# MCU.net
KiCad netlist of a schematic drawn in Altium Designer
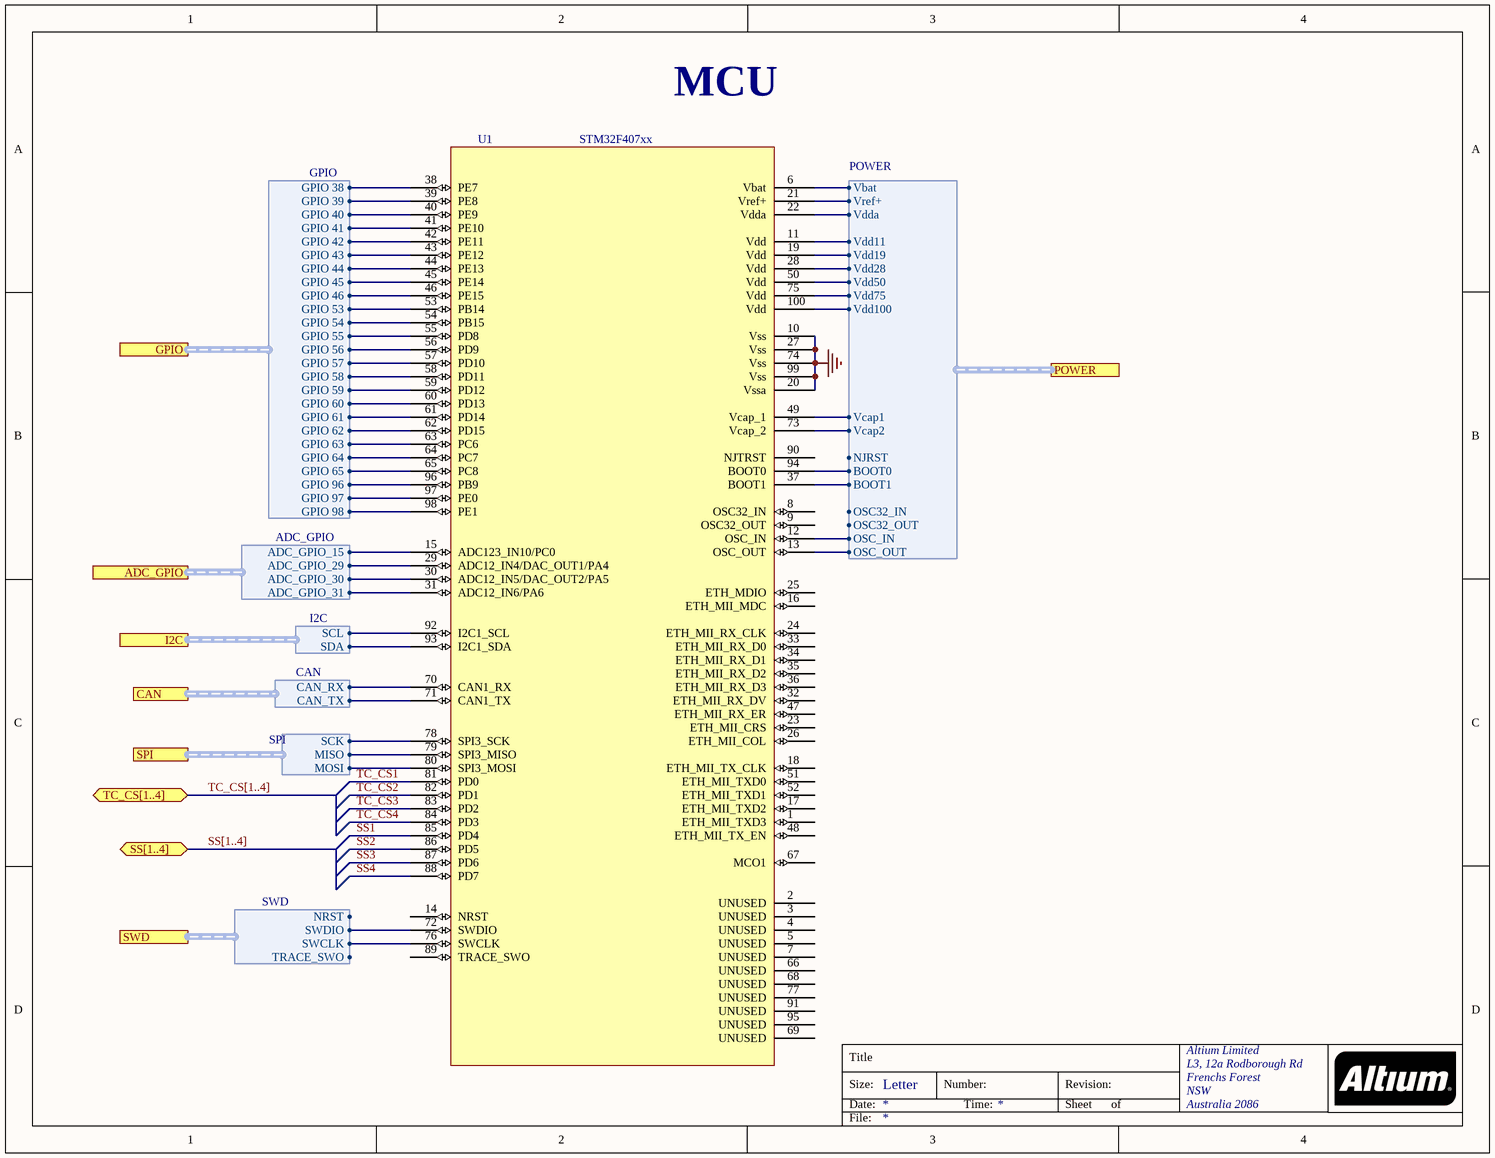
[diagram p0: MCU.SchDoc]

(export (version "E")
  (design (tool "Eeschema 10.0.6"))
  (components
    (comp (ref "U1")
      (value "STM32F407xx")
      (footprint "LQFP100")
      (libsource (lib "LaunchyRIOComponents") (part "STM32F407xx"))
    )
  )
  (nets
    (net (code "8") (name "/ADC_GPIO_15") (class "Default")
      (node (ref "U1") (pin "15") (pinfunction "ADC123_IN10/PC0_15") (pintype "bidirectional"))
    )
    (net (code "9") (name "/ADC_GPIO_29") (class "Default")
      (node (ref "U1") (pin "29") (pinfunction "ADC12_IN4/DAC_OUT1/PA4_29") (pintype "bidirectional"))
    )
    (net (code "10") (name "/ADC_GPIO_30") (class "Default")
      (node (ref "U1") (pin "30") (pinfunction "ADC12_IN5/DAC_OUT2/PA5_30") (pintype "bidirectional"))
    )
    (net (code "11") (name "/ADC_GPIO_31") (class "Default")
      (node (ref "U1") (pin "31") (pinfunction "ADC12_IN6/PA6_31") (pintype "bidirectional"))
    )
    (net (code "12") (name "/BOOT0") (class "Default")
      (node (ref "U1") (pin "94") (pinfunction "BOOT0_94") (pintype "passive"))
    )
    (net (code "13") (name "/BOOT1") (class "Default")
      (node (ref "U1") (pin "37") (pinfunction "BOOT1_37") (pintype "passive"))
    )
    (net (code "14") (name "/CAN_RX") (class "Default")
      (node (ref "U1") (pin "70") (pinfunction "CAN1_RX_70") (pintype "bidirectional"))
    )
    (net (code "15") (name "/CAN_TX") (class "Default")
      (node (ref "U1") (pin "71") (pinfunction "CAN1_TX_71") (pintype "bidirectional"))
    )
    (net (code "16") (name "/GPIO 38") (class "Default")
      (node (ref "U1") (pin "38") (pinfunction "PE7_38") (pintype "bidirectional"))
    )
    (net (code "17") (name "/GPIO 39") (class "Default")
      (node (ref "U1") (pin "39") (pinfunction "PE8_39") (pintype "bidirectional"))
    )
    (net (code "18") (name "/GPIO 40") (class "Default")
      (node (ref "U1") (pin "40") (pinfunction "PE9_40") (pintype "bidirectional"))
    )
    (net (code "19") (name "/GPIO 41") (class "Default")
      (node (ref "U1") (pin "41") (pinfunction "PE10_41") (pintype "bidirectional"))
    )
    (net (code "20") (name "/GPIO 42") (class "Default")
      (node (ref "U1") (pin "42") (pinfunction "PE11_42") (pintype "bidirectional"))
    )
    (net (code "21") (name "/GPIO 43") (class "Default")
      (node (ref "U1") (pin "43") (pinfunction "PE12_43") (pintype "bidirectional"))
    )
    (net (code "22") (name "/GPIO 44") (class "Default")
      (node (ref "U1") (pin "44") (pinfunction "PE13_44") (pintype "bidirectional"))
    )
    (net (code "23") (name "/GPIO 45") (class "Default")
      (node (ref "U1") (pin "45") (pinfunction "PE14_45") (pintype "bidirectional"))
    )
    (net (code "24") (name "/GPIO 46") (class "Default")
      (node (ref "U1") (pin "46") (pinfunction "PE15_46") (pintype "bidirectional"))
    )
    (net (code "25") (name "/GPIO 53") (class "Default")
      (node (ref "U1") (pin "53") (pinfunction "PB14_53") (pintype "bidirectional"))
    )
    (net (code "26") (name "/GPIO 54") (class "Default")
      (node (ref "U1") (pin "54") (pinfunction "PB15_54") (pintype "bidirectional"))
    )
    (net (code "27") (name "/GPIO 55") (class "Default")
      (node (ref "U1") (pin "55") (pinfunction "PD8_55") (pintype "bidirectional"))
    )
    (net (code "28") (name "/GPIO 56") (class "Default")
      (node (ref "U1") (pin "56") (pinfunction "PD9_56") (pintype "bidirectional"))
    )
    (net (code "29") (name "/GPIO 57") (class "Default")
      (node (ref "U1") (pin "57") (pinfunction "PD10_57") (pintype "bidirectional"))
    )
    (net (code "30") (name "/GPIO 58") (class "Default")
      (node (ref "U1") (pin "58") (pinfunction "PD11_58") (pintype "bidirectional"))
    )
    (net (code "31") (name "/GPIO 59") (class "Default")
      (node (ref "U1") (pin "59") (pinfunction "PD12_59") (pintype "bidirectional"))
    )
    (net (code "32") (name "/GPIO 60") (class "Default")
      (node (ref "U1") (pin "60") (pinfunction "PD13_60") (pintype "bidirectional"))
    )
    (net (code "33") (name "/GPIO 61") (class "Default")
      (node (ref "U1") (pin "61") (pinfunction "PD14_61") (pintype "bidirectional"))
    )
    (net (code "34") (name "/GPIO 62") (class "Default")
      (node (ref "U1") (pin "62") (pinfunction "PD15_62") (pintype "bidirectional"))
    )
    (net (code "35") (name "/GPIO 63") (class "Default")
      (node (ref "U1") (pin "63") (pinfunction "PC6_63") (pintype "bidirectional"))
    )
    (net (code "36") (name "/GPIO 64") (class "Default")
      (node (ref "U1") (pin "64") (pinfunction "PC7_64") (pintype "bidirectional"))
    )
    (net (code "37") (name "/GPIO 65") (class "Default")
      (node (ref "U1") (pin "65") (pinfunction "PC8_65") (pintype "bidirectional"))
    )
    (net (code "38") (name "/GPIO 96") (class "Default")
      (node (ref "U1") (pin "96") (pinfunction "PB9_96") (pintype "bidirectional"))
    )
    (net (code "39") (name "/GPIO 97") (class "Default")
      (node (ref "U1") (pin "97") (pinfunction "PE0_97") (pintype "bidirectional"))
    )
    (net (code "40") (name "/GPIO 98") (class "Default")
      (node (ref "U1") (pin "98") (pinfunction "PE1_98") (pintype "bidirectional"))
    )
    (net (code "41") (name "/MISO") (class "Default")
      (node (ref "U1") (pin "79") (pinfunction "SPI3_MISO_79") (pintype "bidirectional"))
    )
    (net (code "42") (name "/MOSI") (class "Default")
      (node (ref "U1") (pin "80") (pinfunction "SPI3_MOSI_80") (pintype "bidirectional"))
    )
    (net (code "43") (name "/OSC_IN") (class "Default")
      (node (ref "U1") (pin "12") (pinfunction "OSC_IN_12") (pintype "bidirectional"))
    )
    (net (code "44") (name "/OSC_OUT") (class "Default")
      (node (ref "U1") (pin "13") (pinfunction "OSC_OUT_13") (pintype "bidirectional"))
    )
    (net (code "45") (name "/SCK") (class "Default")
      (node (ref "U1") (pin "78") (pinfunction "SPI3_SCK_78") (pintype "bidirectional"))
    )
    (net (code "46") (name "/SCL") (class "Default")
      (node (ref "U1") (pin "92") (pinfunction "I2C1_SCL_92") (pintype "bidirectional"))
    )
    (net (code "47") (name "/SDA") (class "Default")
      (node (ref "U1") (pin "93") (pinfunction "I2C1_SDA_93") (pintype "bidirectional"))
    )
    (net (code "48") (name "/SS1") (class "Default")
      (node (ref "U1") (pin "85") (pinfunction "PD4_85") (pintype "bidirectional"))
    )
    (net (code "49") (name "/SS2") (class "Default")
      (node (ref "U1") (pin "86") (pinfunction "PD5_86") (pintype "bidirectional"))
    )
    (net (code "50") (name "/SS3") (class "Default")
      (node (ref "U1") (pin "87") (pinfunction "PD6_87") (pintype "bidirectional"))
    )
    (net (code "51") (name "/SS4") (class "Default")
      (node (ref "U1") (pin "88") (pinfunction "PD7_88") (pintype "bidirectional"))
    )
    (net (code "53") (name "/SWCLK") (class "Default")
      (node (ref "U1") (pin "76") (pinfunction "SWCLK_76") (pintype "bidirectional"))
    )
    (net (code "54") (name "/SWDIO") (class "Default")
      (node (ref "U1") (pin "72") (pinfunction "SWDIO_72") (pintype "bidirectional"))
    )
    (net (code "55") (name "/TC_CS1") (class "Default")
      (node (ref "U1") (pin "81") (pinfunction "PD0_81") (pintype "bidirectional"))
    )
    (net (code "56") (name "/TC_CS2") (class "Default")
      (node (ref "U1") (pin "82") (pinfunction "PD1_82") (pintype "bidirectional"))
    )
    (net (code "57") (name "/TC_CS3") (class "Default")
      (node (ref "U1") (pin "83") (pinfunction "PD2_83") (pintype "bidirectional"))
    )
    (net (code "58") (name "/TC_CS4") (class "Default")
      (node (ref "U1") (pin "84") (pinfunction "PD3_84") (pintype "bidirectional"))
    )
    (net (code "60") (name "/Vbat") (class "Default")
      (node (ref "U1") (pin "6") (pinfunction "Vbat_6") (pintype "power_in"))
    )
    (net (code "61") (name "/Vcap1") (class "Default")
      (node (ref "U1") (pin "49") (pinfunction "Vcap_1_49") (pintype "passive"))
    )
    (net (code "62") (name "/Vcap2") (class "Default")
      (node (ref "U1") (pin "73") (pinfunction "Vcap_2_73") (pintype "passive"))
    )
    (net (code "63") (name "/Vdd11") (class "Default")
      (node (ref "U1") (pin "11") (pinfunction "Vdd_11") (pintype "power_in"))
    )
    (net (code "64") (name "/Vdd19") (class "Default")
      (node (ref "U1") (pin "19") (pinfunction "Vdd_19") (pintype "power_in"))
    )
    (net (code "65") (name "/Vdd28") (class "Default")
      (node (ref "U1") (pin "28") (pinfunction "Vdd_28") (pintype "power_in"))
    )
    (net (code "66") (name "/Vdd50") (class "Default")
      (node (ref "U1") (pin "50") (pinfunction "Vdd_50") (pintype "passive"))
    )
    (net (code "67") (name "/Vdd75") (class "Default")
      (node (ref "U1") (pin "75") (pinfunction "Vdd_75") (pintype "passive"))
    )
    (net (code "68") (name "/Vdd100") (class "Default")
      (node (ref "U1") (pin "100") (pinfunction "Vdd_100") (pintype "passive"))
    )
    (net (code "69") (name "/Vdda") (class "Default")
      (node (ref "U1") (pin "22") (pinfunction "Vdda_22") (pintype "power_in"))
    )
    (net (code "70") (name "/Vref+") (class "Default")
      (node (ref "U1") (pin "21") (pinfunction "Vref+_21") (pintype "power_in"))
    )
    (net (code "78") (name "GND") (class "Default")
      (node (ref "U1") (pin "10") (pinfunction "Vss_10") (pintype "power_in"))
      (node (ref "U1") (pin "20") (pinfunction "Vssa_20") (pintype "power_in"))
      (node (ref "U1") (pin "27") (pinfunction "Vss_27") (pintype "power_in"))
      (node (ref "U1") (pin "74") (pinfunction "Vss_74") (pintype "power_in"))
      (node (ref "U1") (pin "99") (pinfunction "Vss_99") (pintype "passive"))
    )
    (net (code "79") (name "unconnected-(U1-ETH_MDIO-Pad25)") (class "Default")
      (node (ref "U1") (pin "25") (pinfunction "ETH_MDIO_25") (pintype "bidirectional"))
    )
    (net (code "80") (name "unconnected-(U1-ETH_MII_COL-Pad26)") (class "Default")
      (node (ref "U1") (pin "26") (pinfunction "ETH_MII_COL_26") (pintype "bidirectional"))
    )
    (net (code "81") (name "unconnected-(U1-ETH_MII_CRS-Pad23)") (class "Default")
      (node (ref "U1") (pin "23") (pinfunction "ETH_MII_CRS_23") (pintype "bidirectional"))
    )
    (net (code "82") (name "unconnected-(U1-ETH_MII_MDC-Pad16)") (class "Default")
      (node (ref "U1") (pin "16") (pinfunction "ETH_MII_MDC_16") (pintype "bidirectional"))
    )
    (net (code "83") (name "unconnected-(U1-ETH_MII_RX_CLK-Pad24)") (class "Default")
      (node (ref "U1") (pin "24") (pinfunction "ETH_MII_RX_CLK_24") (pintype "bidirectional"))
    )
    (net (code "84") (name "unconnected-(U1-ETH_MII_RX_D0-Pad33)") (class "Default")
      (node (ref "U1") (pin "33") (pinfunction "ETH_MII_RX_D0_33") (pintype "bidirectional"))
    )
    (net (code "85") (name "unconnected-(U1-ETH_MII_RX_D1-Pad34)") (class "Default")
      (node (ref "U1") (pin "34") (pinfunction "ETH_MII_RX_D1_34") (pintype "bidirectional"))
    )
    (net (code "86") (name "unconnected-(U1-ETH_MII_RX_D2-Pad35)") (class "Default")
      (node (ref "U1") (pin "35") (pinfunction "ETH_MII_RX_D2_35") (pintype "bidirectional"))
    )
    (net (code "87") (name "unconnected-(U1-ETH_MII_RX_D3-Pad36)") (class "Default")
      (node (ref "U1") (pin "36") (pinfunction "ETH_MII_RX_D3_36") (pintype "bidirectional"))
    )
    (net (code "88") (name "unconnected-(U1-ETH_MII_RX_DV-Pad32)") (class "Default")
      (node (ref "U1") (pin "32") (pinfunction "ETH_MII_RX_DV_32") (pintype "bidirectional"))
    )
    (net (code "89") (name "unconnected-(U1-ETH_MII_RX_ER-Pad47)") (class "Default")
      (node (ref "U1") (pin "47") (pinfunction "ETH_MII_RX_ER_47") (pintype "bidirectional"))
    )
    (net (code "90") (name "unconnected-(U1-ETH_MII_TXD0-Pad51)") (class "Default")
      (node (ref "U1") (pin "51") (pinfunction "ETH_MII_TXD0_51") (pintype "bidirectional"))
    )
    (net (code "91") (name "unconnected-(U1-ETH_MII_TXD1-Pad52)") (class "Default")
      (node (ref "U1") (pin "52") (pinfunction "ETH_MII_TXD1_52") (pintype "bidirectional"))
    )
    (net (code "92") (name "unconnected-(U1-ETH_MII_TXD2-Pad17)") (class "Default")
      (node (ref "U1") (pin "17") (pinfunction "ETH_MII_TXD2_17") (pintype "bidirectional"))
    )
    (net (code "93") (name "unconnected-(U1-ETH_MII_TXD3-Pad1)") (class "Default")
      (node (ref "U1") (pin "1") (pinfunction "ETH_MII_TXD3_1") (pintype "bidirectional"))
    )
    (net (code "94") (name "unconnected-(U1-ETH_MII_TX_CLK-Pad18)") (class "Default")
      (node (ref "U1") (pin "18") (pinfunction "ETH_MII_TX_CLK_18") (pintype "bidirectional"))
    )
    (net (code "95") (name "unconnected-(U1-ETH_MII_TX_EN-Pad48)") (class "Default")
      (node (ref "U1") (pin "48") (pinfunction "ETH_MII_TX_EN_48") (pintype "bidirectional"))
    )
    (net (code "96") (name "unconnected-(U1-MCO1-Pad67)") (class "Default")
      (node (ref "U1") (pin "67") (pinfunction "MCO1_67") (pintype "bidirectional"))
    )
    (net (code "97") (name "unconnected-(U1-NJTRST-Pad90)") (class "Default")
      (node (ref "U1") (pin "90") (pinfunction "NJTRST_90") (pintype "passive"))
    )
    (net (code "98") (name "unconnected-(U1-NRST-Pad14)") (class "Default")
      (node (ref "U1") (pin "14") (pinfunction "NRST_14") (pintype "bidirectional"))
    )
    (net (code "99") (name "unconnected-(U1-OSC32_IN-Pad8)") (class "Default")
      (node (ref "U1") (pin "8") (pinfunction "OSC32_IN_8") (pintype "bidirectional"))
    )
    (net (code "100") (name "unconnected-(U1-OSC32_OUT-Pad9)") (class "Default")
      (node (ref "U1") (pin "9") (pinfunction "OSC32_OUT_9") (pintype "bidirectional"))
    )
    (net (code "101") (name "unconnected-(U1-TRACE_SWO-Pad89)") (class "Default")
      (node (ref "U1") (pin "89") (pinfunction "TRACE_SWO_89") (pintype "bidirectional"))
    )
    (net (code "102") (name "unconnected-(U1-UNUSED-Pad2)") (class "Default")
      (node (ref "U1") (pin "2") (pinfunction "UNUSED_2") (pintype "passive"))
    )
    (net (code "103") (name "unconnected-(U1-UNUSED-Pad3)") (class "Default")
      (node (ref "U1") (pin "3") (pinfunction "UNUSED_3") (pintype "passive"))
    )
    (net (code "104") (name "unconnected-(U1-UNUSED-Pad4)") (class "Default")
      (node (ref "U1") (pin "4") (pinfunction "UNUSED_4") (pintype "passive"))
    )
    (net (code "105") (name "unconnected-(U1-UNUSED-Pad5)") (class "Default")
      (node (ref "U1") (pin "5") (pinfunction "UNUSED_5") (pintype "passive"))
    )
    (net (code "106") (name "unconnected-(U1-UNUSED-Pad7)") (class "Default")
      (node (ref "U1") (pin "7") (pinfunction "UNUSED_7") (pintype "passive"))
    )
    (net (code "107") (name "unconnected-(U1-UNUSED-Pad66)") (class "Default")
      (node (ref "U1") (pin "66") (pinfunction "UNUSED_66") (pintype "passive"))
    )
    (net (code "108") (name "unconnected-(U1-UNUSED-Pad68)") (class "Default")
      (node (ref "U1") (pin "68") (pinfunction "UNUSED_68") (pintype "passive"))
    )
    (net (code "109") (name "unconnected-(U1-UNUSED-Pad69)") (class "Default")
      (node (ref "U1") (pin "69") (pinfunction "UNUSED_69") (pintype "passive"))
    )
    (net (code "110") (name "unconnected-(U1-UNUSED-Pad77)") (class "Default")
      (node (ref "U1") (pin "77") (pinfunction "UNUSED_77") (pintype "passive"))
    )
    (net (code "111") (name "unconnected-(U1-UNUSED-Pad91)") (class "Default")
      (node (ref "U1") (pin "91") (pinfunction "UNUSED_91") (pintype "passive"))
    )
    (net (code "112") (name "unconnected-(U1-UNUSED-Pad95)") (class "Default")
      (node (ref "U1") (pin "95") (pinfunction "UNUSED_95") (pintype "passive"))
    )
  )
)
